# ardcore_V1.net
KiCad netlist of a schematic drawn in EAGLE
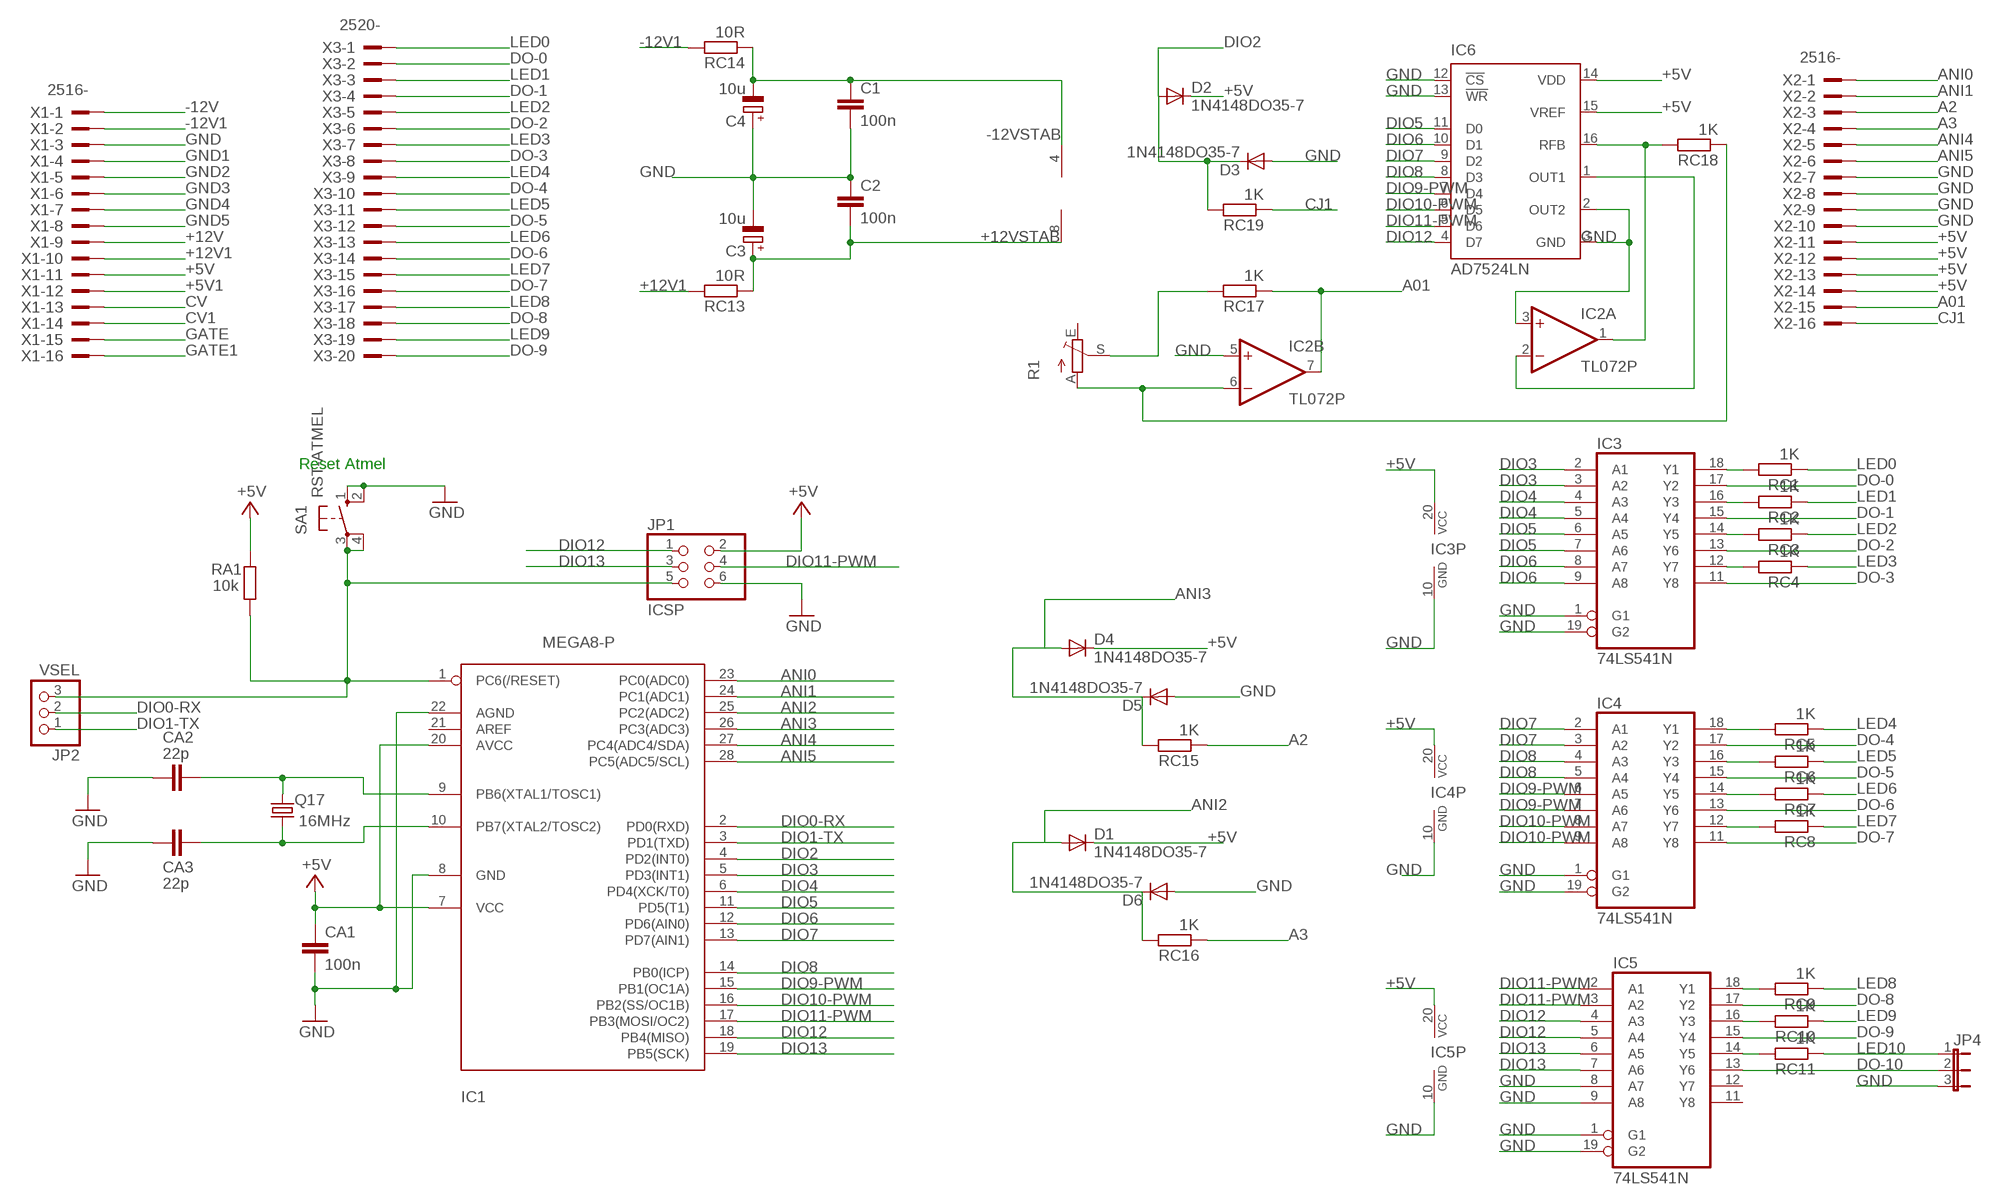
[diagram p0: schematic, sheet 1]

(export (version "E")
  (design (tool "Eeschema 10.0.6"))
  (components
    (comp (ref "C1")
      (value "100n")
      (footprint "eagle-import:C050-025X075")
      (libsource (lib "eagle-import") (part "C-EU050-025X075"))
    )
    (comp (ref "C2")
      (value "100n")
      (footprint "eagle-import:C050-025X075")
      (libsource (lib "eagle-import") (part "C-EU050-025X075"))
    )
    (comp (ref "C3")
      (value "10u")
      (footprint "eagle-import:E2,5-7")
      (libsource (lib "eagle-import") (part "CPOL-EUE2.5-7"))
    )
    (comp (ref "C4")
      (value "10u")
      (footprint "eagle-import:E2,5-7")
      (libsource (lib "eagle-import") (part "CPOL-EUE2.5-7"))
    )
    (comp (ref "CA1")
      (value "100n")
      (footprint "eagle-import:C050-025X075")
      (libsource (lib "eagle-import") (part "C-EU050-025X075"))
    )
    (comp (ref "CA2")
      (value "22p")
      (footprint "eagle-import:C050-025X075")
      (libsource (lib "eagle-import") (part "C-EU050-025X075"))
    )
    (comp (ref "CA3")
      (value "22p")
      (footprint "eagle-import:C050-025X075")
      (libsource (lib "eagle-import") (part "C-EU050-025X075"))
    )
    (comp (ref "D1")
      (value "1N4148DO35-7")
      (footprint "eagle-import:DO35-7")
      (libsource (lib "eagle-import") (part "1N4148DO35-7"))
    )
    (comp (ref "D2")
      (value "1N4148DO35-7")
      (footprint "eagle-import:DO35-7")
      (libsource (lib "eagle-import") (part "1N4148DO35-7"))
    )
    (comp (ref "D3")
      (value "1N4148DO35-7")
      (footprint "eagle-import:DO35-7")
      (libsource (lib "eagle-import") (part "1N4148DO35-7"))
    )
    (comp (ref "D4")
      (value "1N4148DO35-7")
      (footprint "eagle-import:DO35-7")
      (libsource (lib "eagle-import") (part "1N4148DO35-7"))
    )
    (comp (ref "D5")
      (value "1N4148DO35-7")
      (footprint "eagle-import:DO35-7")
      (libsource (lib "eagle-import") (part "1N4148DO35-7"))
    )
    (comp (ref "D6")
      (value "1N4148DO35-7")
      (footprint "eagle-import:DO35-7")
      (libsource (lib "eagle-import") (part "1N4148DO35-7"))
    )
    (comp (ref "IC1")
      (value "MEGA8-P")
      (footprint "eagle-import:DIL28-3")
      (libsource (lib "eagle-import") (part "MEGA8-P"))
    )
    (comp (ref "IC2")
      (value "TL072P")
      (footprint "eagle-import:DIL08")
      (libsource (lib "eagle-import") (part "TL072P"))
    )
    (comp (ref "IC3")
      (value "74LS541N")
      (footprint "eagle-import:DIL20")
      (libsource (lib "eagle-import") (part "74541NLS"))
    )
    (comp (ref "IC4")
      (value "74LS541N")
      (footprint "eagle-import:DIL20")
      (libsource (lib "eagle-import") (part "74541NLS"))
    )
    (comp (ref "IC5")
      (value "74LS541N")
      (footprint "eagle-import:DIL20")
      (libsource (lib "eagle-import") (part "74541NLS"))
    )
    (comp (ref "IC6")
      (value "AD7524LN")
      (footprint "eagle-import:DIL16")
      (fields (field (name "MF") "ALTERA CORPORATION") (field (name "MPN") "AD7524LNZ"))
      (libsource (lib "eagle-import") (part "AD7524NL"))
    )
    (comp (ref "JP1")
      (value "ICSP")
      (footprint "eagle-import:2X03")
      (libsource (lib "eagle-import") (part "PINHD-2X3"))
    )
    (comp (ref "JP2")
      (value "VSEL")
      (footprint "eagle-import:1X03")
      (libsource (lib "eagle-import") (part "PINHD-1X3"))
    )
    (comp (ref "JP4")
      (value "JP2E")
      (footprint "eagle-import:JP2")
      (libsource (lib "eagle-import") (part "JP2E"))
    )
    (comp (ref "Q17")
      (value "16MHz")
      (footprint "eagle-import:HC49_S")
      (libsource (lib "eagle-import") (part "CRYSTALHC49S"))
    )
    (comp (ref "R1")
      (value "TRIM_EU-B64Y")
      (footprint "eagle-import:B64Y")
      (libsource (lib "eagle-import") (part "TRIM_EU-B64Y"))
    )
    (comp (ref "RA1")
      (value "10k")
      (footprint "eagle-import:0207_10")
      (libsource (lib "eagle-import") (part "R-EU_0207/10"))
    )
    (comp (ref "RC1")
      (value "1K")
      (footprint "eagle-import:0207_10")
      (libsource (lib "eagle-import") (part "R-EU_0207/10"))
    )
    (comp (ref "RC2")
      (value "1K")
      (footprint "eagle-import:0207_10")
      (libsource (lib "eagle-import") (part "R-EU_0207/10"))
    )
    (comp (ref "RC3")
      (value "1K")
      (footprint "eagle-import:0207_10")
      (libsource (lib "eagle-import") (part "R-EU_0207/10"))
    )
    (comp (ref "RC4")
      (value "1K")
      (footprint "eagle-import:0207_10")
      (libsource (lib "eagle-import") (part "R-EU_0207/10"))
    )
    (comp (ref "RC5")
      (value "1K")
      (footprint "eagle-import:0207_10")
      (libsource (lib "eagle-import") (part "R-EU_0207/10"))
    )
    (comp (ref "RC6")
      (value "1K")
      (footprint "eagle-import:0207_10")
      (libsource (lib "eagle-import") (part "R-EU_0207/10"))
    )
    (comp (ref "RC7")
      (value "1K")
      (footprint "eagle-import:0207_10")
      (libsource (lib "eagle-import") (part "R-EU_0207/10"))
    )
    (comp (ref "RC8")
      (value "1K")
      (footprint "eagle-import:0207_10")
      (libsource (lib "eagle-import") (part "R-EU_0207/10"))
    )
    (comp (ref "RC9")
      (value "1K")
      (footprint "eagle-import:0207_10")
      (libsource (lib "eagle-import") (part "R-EU_0207/10"))
    )
    (comp (ref "RC10")
      (value "1K")
      (footprint "eagle-import:0207_10")
      (libsource (lib "eagle-import") (part "R-EU_0207/10"))
    )
    (comp (ref "RC11")
      (value "1K")
      (footprint "eagle-import:0207_10")
      (libsource (lib "eagle-import") (part "R-EU_0207/10"))
    )
    (comp (ref "RC13")
      (value "10R")
      (footprint "eagle-import:0207_10")
      (libsource (lib "eagle-import") (part "R-EU_0207/10"))
    )
    (comp (ref "RC14")
      (value "10R")
      (footprint "eagle-import:0207_10")
      (libsource (lib "eagle-import") (part "R-EU_0207/10"))
    )
    (comp (ref "RC15")
      (value "1K")
      (footprint "eagle-import:0207_10")
      (libsource (lib "eagle-import") (part "R-EU_0207/10"))
    )
    (comp (ref "RC16")
      (value "1K")
      (footprint "eagle-import:0207_10")
      (libsource (lib "eagle-import") (part "R-EU_0207/10"))
    )
    (comp (ref "RC17")
      (value "1K")
      (footprint "eagle-import:0207_10")
      (libsource (lib "eagle-import") (part "R-EU_0207/10"))
    )
    (comp (ref "RC18")
      (value "1K")
      (footprint "eagle-import:0207_10")
      (libsource (lib "eagle-import") (part "R-EU_0207/10"))
    )
    (comp (ref "RC19")
      (value "1K")
      (footprint "eagle-import:0207_10")
      (libsource (lib "eagle-import") (part "R-EU_0207/10"))
    )
    (comp (ref "SA1")
      (value "RST-ATMEL")
      (footprint "eagle-import:B3F-10XX")
      (libsource (lib "eagle-import") (part "10-XX"))
    )
    (comp (ref "X1")
      (value "2516-")
      (footprint "eagle-import:PAK100_2500-16")
      (libsource (lib "eagle-import") (part "2516-"))
    )
    (comp (ref "X2")
      (value "2516-")
      (footprint "eagle-import:PAK100_2500-16")
      (libsource (lib "eagle-import") (part "2516-"))
    )
    (comp (ref "X3")
      (value "2520-")
      (footprint "eagle-import:PAK100_2500-20")
      (libsource (lib "eagle-import") (part "2520-"))
    )
  )
  (nets
    (net (code "1") (name "+5V") (class "Default")
      (node (ref "CA1") (pin "1") (pinfunction "1_1") (pintype "passive"))
      (node (ref "D1") (pin "C") (pinfunction "C_C") (pintype "passive"))
      (node (ref "D2") (pin "C") (pinfunction "C_C") (pintype "passive"))
      (node (ref "D4") (pin "C") (pinfunction "C_C") (pintype "passive"))
      (node (ref "IC1") (pin "20") (pinfunction "AVCC_20") (pintype "power_in"))
      (node (ref "IC1") (pin "7") (pinfunction "VCC_7") (pintype "power_in"))
      (node (ref "IC3") (pin "20") (pinfunction "VCC_20") (pintype "power_in"))
      (node (ref "IC4") (pin "20") (pinfunction "VCC_20") (pintype "power_in"))
      (node (ref "IC5") (pin "20") (pinfunction "VCC_20") (pintype "power_in"))
      (node (ref "IC6") (pin "14") (pinfunction "VDD_14") (pintype "power_in"))
      (node (ref "IC6") (pin "15") (pinfunction "VREF_15") (pintype "input"))
      (node (ref "JP1") (pin "2") (pinfunction "2_2") (pintype "passive"))
      (node (ref "RA1") (pin "1") (pinfunction "1_1") (pintype "passive"))
      (node (ref "X1") (pin "11") (pinfunction "KL_11") (pintype "passive"))
      (node (ref "X2") (pin "11") (pinfunction "KL_11") (pintype "passive"))
      (node (ref "X2") (pin "12") (pinfunction "KL_12") (pintype "passive"))
      (node (ref "X2") (pin "13") (pinfunction "KL_13") (pintype "passive"))
      (node (ref "X2") (pin "14") (pinfunction "KL_14") (pintype "passive"))
    )
    (net (code "2") (name "/+5V1") (class "Default")
      (node (ref "X1") (pin "12") (pinfunction "KL_12") (pintype "passive"))
    )
    (net (code "3") (name "/+12V") (class "Default")
      (node (ref "X1") (pin "9") (pinfunction "KL_9") (pintype "passive"))
    )
    (net (code "4") (name "/+12V1") (class "Default")
      (node (ref "RC13") (pin "2") (pinfunction "2_2") (pintype "passive"))
      (node (ref "X1") (pin "10") (pinfunction "KL_10") (pintype "passive"))
    )
    (net (code "5") (name "/+12VSTAB") (class "Default")
      (node (ref "C2") (pin "2") (pinfunction "2_2") (pintype "passive"))
      (node (ref "C3") (pin "+") (pinfunction "+_+") (pintype "passive"))
      (node (ref "IC2") (pin "8") (pinfunction "V+_8") (pintype "power_in"))
      (node (ref "RC13") (pin "1") (pinfunction "1_1") (pintype "passive"))
    )
    (net (code "6") (name "/-12V") (class "Default")
      (node (ref "X1") (pin "1") (pinfunction "KL_1") (pintype "passive"))
    )
    (net (code "7") (name "/-12V1") (class "Default")
      (node (ref "RC14") (pin "2") (pinfunction "2_2") (pintype "passive"))
      (node (ref "X1") (pin "2") (pinfunction "KL_2") (pintype "passive"))
    )
    (net (code "8") (name "/-12VSTAB") (class "Default")
      (node (ref "C1") (pin "1") (pinfunction "1_1") (pintype "passive"))
      (node (ref "C4") (pin "-") (pinfunction "-_-") (pintype "passive"))
      (node (ref "IC2") (pin "4") (pinfunction "V-_4") (pintype "power_in"))
      (node (ref "RC14") (pin "1") (pinfunction "1_1") (pintype "passive"))
    )
    (net (code "9") (name "/A01") (class "Default")
      (node (ref "IC2") (pin "7") (pinfunction "OUT_7") (pintype "output"))
      (node (ref "RC17") (pin "1") (pinfunction "1_1") (pintype "passive"))
      (node (ref "X2") (pin "15") (pinfunction "KL_15") (pintype "passive"))
    )
    (net (code "10") (name "/A2") (class "Default")
      (node (ref "RC15") (pin "1") (pinfunction "1_1") (pintype "passive"))
      (node (ref "X2") (pin "3") (pinfunction "KL_3") (pintype "passive"))
    )
    (net (code "11") (name "/A3") (class "Default")
      (node (ref "RC16") (pin "1") (pinfunction "1_1") (pintype "passive"))
      (node (ref "X2") (pin "4") (pinfunction "KL_4") (pintype "passive"))
    )
    (net (code "12") (name "/ANI0") (class "Default")
      (node (ref "IC1") (pin "23") (pinfunction "PC0(ADC0)_23") (pintype "bidirectional"))
      (node (ref "X2") (pin "1") (pinfunction "KL_1") (pintype "passive"))
    )
    (net (code "13") (name "/ANI1") (class "Default")
      (node (ref "IC1") (pin "24") (pinfunction "PC1(ADC1)_24") (pintype "bidirectional"))
      (node (ref "X2") (pin "2") (pinfunction "KL_2") (pintype "passive"))
    )
    (net (code "14") (name "/ANI2") (class "Default")
      (node (ref "D1") (pin "A") (pinfunction "A_A") (pintype "passive"))
      (node (ref "D6") (pin "C") (pinfunction "C_C") (pintype "passive"))
      (node (ref "IC1") (pin "25") (pinfunction "PC2(ADC2)_25") (pintype "bidirectional"))
      (node (ref "RC16") (pin "2") (pinfunction "2_2") (pintype "passive"))
    )
    (net (code "15") (name "/ANI3") (class "Default")
      (node (ref "D4") (pin "A") (pinfunction "A_A") (pintype "passive"))
      (node (ref "D5") (pin "C") (pinfunction "C_C") (pintype "passive"))
      (node (ref "IC1") (pin "26") (pinfunction "PC3(ADC3)_26") (pintype "bidirectional"))
      (node (ref "RC15") (pin "2") (pinfunction "2_2") (pintype "passive"))
    )
    (net (code "16") (name "/ANI4") (class "Default")
      (node (ref "IC1") (pin "27") (pinfunction "PC4(ADC4/SDA)_27") (pintype "bidirectional"))
      (node (ref "X2") (pin "5") (pinfunction "KL_5") (pintype "passive"))
    )
    (net (code "17") (name "/ANI5") (class "Default")
      (node (ref "IC1") (pin "28") (pinfunction "PC5(ADC5/SCL)_28") (pintype "bidirectional"))
      (node (ref "X2") (pin "6") (pinfunction "KL_6") (pintype "passive"))
    )
    (net (code "18") (name "/CJ1") (class "Default")
      (node (ref "RC19") (pin "1") (pinfunction "1_1") (pintype "passive"))
      (node (ref "X2") (pin "16") (pinfunction "KL_16") (pintype "passive"))
    )
    (net (code "19") (name "/CV") (class "Default")
      (node (ref "X1") (pin "13") (pinfunction "KL_13") (pintype "passive"))
    )
    (net (code "20") (name "/CV1") (class "Default")
      (node (ref "X1") (pin "14") (pinfunction "KL_14") (pintype "passive"))
    )
    (net (code "21") (name "/DIO0-RX") (class "Default")
      (node (ref "IC1") (pin "2") (pinfunction "PD0(RXD)_2") (pintype "bidirectional"))
      (node (ref "JP2") (pin "2") (pinfunction "2_2") (pintype "passive"))
    )
    (net (code "22") (name "/DIO1-TX") (class "Default")
      (node (ref "IC1") (pin "3") (pinfunction "PD1(TXD)_3") (pintype "bidirectional"))
      (node (ref "JP2") (pin "1") (pinfunction "1_1") (pintype "passive"))
    )
    (net (code "23") (name "/DIO2") (class "Default")
      (node (ref "D2") (pin "A") (pinfunction "A_A") (pintype "passive"))
      (node (ref "D3") (pin "C") (pinfunction "C_C") (pintype "passive"))
      (node (ref "IC1") (pin "4") (pinfunction "PD2(INT0)_4") (pintype "bidirectional"))
      (node (ref "RC19") (pin "2") (pinfunction "2_2") (pintype "passive"))
    )
    (net (code "24") (name "/DIO3") (class "Default")
      (node (ref "IC1") (pin "5") (pinfunction "PD3(INT1)_5") (pintype "bidirectional"))
      (node (ref "IC3") (pin "2") (pinfunction "A1_2") (pintype "input"))
      (node (ref "IC3") (pin "3") (pinfunction "A2_3") (pintype "input"))
    )
    (net (code "25") (name "/DIO4") (class "Default")
      (node (ref "IC1") (pin "6") (pinfunction "PD4(XCK/T0)_6") (pintype "bidirectional"))
      (node (ref "IC3") (pin "4") (pinfunction "A3_4") (pintype "input"))
      (node (ref "IC3") (pin "5") (pinfunction "A4_5") (pintype "input"))
    )
    (net (code "26") (name "/DIO5") (class "Default")
      (node (ref "IC1") (pin "11") (pinfunction "PD5(T1)_11") (pintype "bidirectional"))
      (node (ref "IC3") (pin "6") (pinfunction "A5_6") (pintype "input"))
      (node (ref "IC3") (pin "7") (pinfunction "A6_7") (pintype "input"))
      (node (ref "IC6") (pin "11") (pinfunction "D0_11") (pintype "input"))
    )
    (net (code "27") (name "/DIO6") (class "Default")
      (node (ref "IC1") (pin "12") (pinfunction "PD6(AIN0)_12") (pintype "bidirectional"))
      (node (ref "IC3") (pin "8") (pinfunction "A7_8") (pintype "input"))
      (node (ref "IC3") (pin "9") (pinfunction "A8_9") (pintype "input"))
      (node (ref "IC6") (pin "10") (pinfunction "D1_10") (pintype "input"))
    )
    (net (code "28") (name "/DIO7") (class "Default")
      (node (ref "IC1") (pin "13") (pinfunction "PD7(AIN1)_13") (pintype "bidirectional"))
      (node (ref "IC4") (pin "2") (pinfunction "A1_2") (pintype "input"))
      (node (ref "IC4") (pin "3") (pinfunction "A2_3") (pintype "input"))
      (node (ref "IC6") (pin "9") (pinfunction "D2_9") (pintype "input"))
    )
    (net (code "29") (name "/DIO8") (class "Default")
      (node (ref "IC1") (pin "14") (pinfunction "PB0(ICP)_14") (pintype "bidirectional"))
      (node (ref "IC4") (pin "4") (pinfunction "A3_4") (pintype "input"))
      (node (ref "IC4") (pin "5") (pinfunction "A4_5") (pintype "input"))
      (node (ref "IC6") (pin "8") (pinfunction "D3_8") (pintype "input"))
    )
    (net (code "30") (name "/DIO9-PWM") (class "Default")
      (node (ref "IC1") (pin "15") (pinfunction "PB1(OC1A)_15") (pintype "bidirectional"))
      (node (ref "IC4") (pin "6") (pinfunction "A5_6") (pintype "input"))
      (node (ref "IC4") (pin "7") (pinfunction "A6_7") (pintype "input"))
      (node (ref "IC6") (pin "7") (pinfunction "D4_7") (pintype "input"))
    )
    (net (code "31") (name "/DIO10-PWM") (class "Default")
      (node (ref "IC1") (pin "16") (pinfunction "PB2(SS/OC1B)_16") (pintype "bidirectional"))
      (node (ref "IC4") (pin "8") (pinfunction "A7_8") (pintype "input"))
      (node (ref "IC4") (pin "9") (pinfunction "A8_9") (pintype "input"))
      (node (ref "IC6") (pin "6") (pinfunction "D5_6") (pintype "input"))
    )
    (net (code "32") (name "/DIO11-PWM") (class "Default")
      (node (ref "IC1") (pin "17") (pinfunction "PB3(MOSI/OC2)_17") (pintype "bidirectional"))
      (node (ref "IC5") (pin "2") (pinfunction "A1_2") (pintype "input"))
      (node (ref "IC5") (pin "3") (pinfunction "A2_3") (pintype "input"))
      (node (ref "IC6") (pin "5") (pinfunction "D6_5") (pintype "input"))
      (node (ref "JP1") (pin "4") (pinfunction "4_4") (pintype "passive"))
    )
    (net (code "33") (name "/DIO12") (class "Default")
      (node (ref "IC1") (pin "18") (pinfunction "PB4(MISO)_18") (pintype "bidirectional"))
      (node (ref "IC5") (pin "4") (pinfunction "A3_4") (pintype "input"))
      (node (ref "IC5") (pin "5") (pinfunction "A4_5") (pintype "input"))
      (node (ref "IC6") (pin "4") (pinfunction "D7_4") (pintype "input"))
      (node (ref "JP1") (pin "1") (pinfunction "1_1") (pintype "passive"))
    )
    (net (code "34") (name "/DIO13") (class "Default")
      (node (ref "IC1") (pin "19") (pinfunction "PB5(SCK)_19") (pintype "bidirectional"))
      (node (ref "IC5") (pin "6") (pinfunction "A5_6") (pintype "input"))
      (node (ref "IC5") (pin "7") (pinfunction "A6_7") (pintype "input"))
      (node (ref "JP1") (pin "3") (pinfunction "3_3") (pintype "passive"))
    )
    (net (code "35") (name "/DO-0") (class "Default")
      (node (ref "IC3") (pin "17") (pinfunction "Y2_17") (pintype "tri_state"))
      (node (ref "X3") (pin "2") (pinfunction "KL_2") (pintype "passive"))
    )
    (net (code "36") (name "/DO-1") (class "Default")
      (node (ref "IC3") (pin "15") (pinfunction "Y4_15") (pintype "tri_state"))
      (node (ref "X3") (pin "4") (pinfunction "KL_4") (pintype "passive"))
    )
    (net (code "37") (name "/DO-2") (class "Default")
      (node (ref "IC3") (pin "13") (pinfunction "Y6_13") (pintype "tri_state"))
      (node (ref "X3") (pin "6") (pinfunction "KL_6") (pintype "passive"))
    )
    (net (code "38") (name "/DO-3") (class "Default")
      (node (ref "IC3") (pin "11") (pinfunction "Y8_11") (pintype "tri_state"))
      (node (ref "X3") (pin "8") (pinfunction "KL_8") (pintype "passive"))
    )
    (net (code "39") (name "/DO-4") (class "Default")
      (node (ref "IC4") (pin "17") (pinfunction "Y2_17") (pintype "tri_state"))
      (node (ref "X3") (pin "10") (pinfunction "KL_10") (pintype "passive"))
    )
    (net (code "40") (name "/DO-5") (class "Default")
      (node (ref "IC4") (pin "15") (pinfunction "Y4_15") (pintype "tri_state"))
      (node (ref "X3") (pin "12") (pinfunction "KL_12") (pintype "passive"))
    )
    (net (code "41") (name "/DO-6") (class "Default")
      (node (ref "IC4") (pin "13") (pinfunction "Y6_13") (pintype "tri_state"))
      (node (ref "X3") (pin "14") (pinfunction "KL_14") (pintype "passive"))
    )
    (net (code "42") (name "/DO-7") (class "Default")
      (node (ref "IC4") (pin "11") (pinfunction "Y8_11") (pintype "tri_state"))
      (node (ref "X3") (pin "16") (pinfunction "KL_16") (pintype "passive"))
    )
    (net (code "43") (name "/DO-8") (class "Default")
      (node (ref "IC5") (pin "17") (pinfunction "Y2_17") (pintype "tri_state"))
      (node (ref "X3") (pin "18") (pinfunction "KL_18") (pintype "passive"))
    )
    (net (code "44") (name "/DO-9") (class "Default")
      (node (ref "IC5") (pin "15") (pinfunction "Y4_15") (pintype "tri_state"))
      (node (ref "X3") (pin "20") (pinfunction "KL_20") (pintype "passive"))
    )
    (net (code "45") (name "/DO-10") (class "Default")
      (node (ref "IC5") (pin "13") (pinfunction "Y6_13") (pintype "tri_state"))
      (node (ref "JP4") (pin "2") (pinfunction "2_2") (pintype "passive"))
    )
    (net (code "46") (name "/GATE") (class "Default")
      (node (ref "X1") (pin "15") (pinfunction "KL_15") (pintype "passive"))
    )
    (net (code "47") (name "/GATE1") (class "Default")
      (node (ref "X1") (pin "16") (pinfunction "KL_16") (pintype "passive"))
    )
    (net (code "48") (name "/GND1") (class "Default")
      (node (ref "X1") (pin "4") (pinfunction "KL_4") (pintype "passive"))
    )
    (net (code "49") (name "/GND2") (class "Default")
      (node (ref "X1") (pin "5") (pinfunction "KL_5") (pintype "passive"))
    )
    (net (code "50") (name "/GND3") (class "Default")
      (node (ref "X1") (pin "6") (pinfunction "KL_6") (pintype "passive"))
    )
    (net (code "51") (name "/GND4") (class "Default")
      (node (ref "X1") (pin "7") (pinfunction "KL_7") (pintype "passive"))
    )
    (net (code "52") (name "/GND5") (class "Default")
      (node (ref "X1") (pin "8") (pinfunction "KL_8") (pintype "passive"))
    )
    (net (code "53") (name "/LED0") (class "Default")
      (node (ref "RC1") (pin "1") (pinfunction "1_1") (pintype "passive"))
      (node (ref "X3") (pin "1") (pinfunction "KL_1") (pintype "passive"))
    )
    (net (code "54") (name "/LED1") (class "Default")
      (node (ref "RC2") (pin "1") (pinfunction "1_1") (pintype "passive"))
      (node (ref "X3") (pin "3") (pinfunction "KL_3") (pintype "passive"))
    )
    (net (code "55") (name "/LED2") (class "Default")
      (node (ref "RC3") (pin "1") (pinfunction "1_1") (pintype "passive"))
      (node (ref "X3") (pin "5") (pinfunction "KL_5") (pintype "passive"))
    )
    (net (code "56") (name "/LED3") (class "Default")
      (node (ref "RC4") (pin "1") (pinfunction "1_1") (pintype "passive"))
      (node (ref "X3") (pin "7") (pinfunction "KL_7") (pintype "passive"))
    )
    (net (code "57") (name "/LED4") (class "Default")
      (node (ref "RC5") (pin "1") (pinfunction "1_1") (pintype "passive"))
      (node (ref "X3") (pin "9") (pinfunction "KL_9") (pintype "passive"))
    )
    (net (code "58") (name "/LED5") (class "Default")
      (node (ref "RC6") (pin "1") (pinfunction "1_1") (pintype "passive"))
      (node (ref "X3") (pin "11") (pinfunction "KL_11") (pintype "passive"))
    )
    (net (code "59") (name "/LED6") (class "Default")
      (node (ref "RC7") (pin "1") (pinfunction "1_1") (pintype "passive"))
      (node (ref "X3") (pin "13") (pinfunction "KL_13") (pintype "passive"))
    )
    (net (code "60") (name "/LED7") (class "Default")
      (node (ref "RC8") (pin "1") (pinfunction "1_1") (pintype "passive"))
      (node (ref "X3") (pin "15") (pinfunction "KL_15") (pintype "passive"))
    )
    (net (code "61") (name "/LED8") (class "Default")
      (node (ref "RC9") (pin "1") (pinfunction "1_1") (pintype "passive"))
      (node (ref "X3") (pin "17") (pinfunction "KL_17") (pintype "passive"))
    )
    (net (code "62") (name "/LED9") (class "Default")
      (node (ref "RC10") (pin "1") (pinfunction "1_1") (pintype "passive"))
      (node (ref "X3") (pin "19") (pinfunction "KL_19") (pintype "passive"))
    )
    (net (code "63") (name "/LED10") (class "Default")
      (node (ref "JP4") (pin "1") (pinfunction "1_1") (pintype "passive"))
      (node (ref "RC11") (pin "1") (pinfunction "1_1") (pintype "passive"))
    )
    (net (code "64") (name "GND") (class "Default")
      (node (ref "C1") (pin "2") (pinfunction "2_2") (pintype "passive"))
      (node (ref "C2") (pin "1") (pinfunction "1_1") (pintype "passive"))
      (node (ref "C3") (pin "-") (pinfunction "-_-") (pintype "passive"))
      (node (ref "C4") (pin "+") (pinfunction "+_+") (pintype "passive"))
      (node (ref "CA1") (pin "2") (pinfunction "2_2") (pintype "passive"))
      (node (ref "CA2") (pin "2") (pinfunction "2_2") (pintype "passive"))
      (node (ref "CA3") (pin "2") (pinfunction "2_2") (pintype "passive"))
      (node (ref "D3") (pin "A") (pinfunction "A_A") (pintype "passive"))
      (node (ref "D5") (pin "A") (pinfunction "A_A") (pintype "passive"))
      (node (ref "D6") (pin "A") (pinfunction "A_A") (pintype "passive"))
      (node (ref "IC1") (pin "22") (pinfunction "AGND_22") (pintype "power_in"))
      (node (ref "IC1") (pin "8") (pinfunction "GND_8") (pintype "power_in"))
      (node (ref "IC2") (pin "3") (pinfunction "+IN_3") (pintype "input"))
      (node (ref "IC2") (pin "5") (pinfunction "+IN_5") (pintype "input"))
      (node (ref "IC3") (pin "1") (pinfunction "G1_1") (pintype "input"))
      (node (ref "IC3") (pin "10") (pinfunction "GND_10") (pintype "power_in"))
      (node (ref "IC3") (pin "19") (pinfunction "G2_19") (pintype "input"))
      (node (ref "IC4") (pin "1") (pinfunction "G1_1") (pintype "input"))
      (node (ref "IC4") (pin "10") (pinfunction "GND_10") (pintype "power_in"))
      (node (ref "IC4") (pin "19") (pinfunction "G2_19") (pintype "input"))
      (node (ref "IC5") (pin "1") (pinfunction "G1_1") (pintype "input"))
      (node (ref "IC5") (pin "10") (pinfunction "GND_10") (pintype "power_in"))
      (node (ref "IC5") (pin "19") (pinfunction "G2_19") (pintype "input"))
      (node (ref "IC5") (pin "8") (pinfunction "A7_8") (pintype "input"))
      (node (ref "IC5") (pin "9") (pinfunction "A8_9") (pintype "input"))
      (node (ref "IC6") (pin "12") (pinfunction "~{CS}_12") (pintype "input"))
      (node (ref "IC6") (pin "13") (pinfunction "~{WR}_13") (pintype "input"))
      (node (ref "IC6") (pin "2") (pinfunction "OUT2_2") (pintype "passive"))
      (node (ref "IC6") (pin "3") (pinfunction "GND_3") (pintype "power_in"))
      (node (ref "JP1") (pin "6") (pinfunction "6_6") (pintype "passive"))
      (node (ref "JP4") (pin "3") (pinfunction "3_3") (pintype "passive"))
      (node (ref "SA1") (pin "1") (pinfunction "S_1") (pintype "passive"))
      (node (ref "SA1") (pin "2") (pinfunction "S1_2") (pintype "passive"))
      (node (ref "X1") (pin "3") (pinfunction "KL_3") (pintype "passive"))
      (node (ref "X2") (pin "10") (pinfunction "KL_10") (pintype "passive"))
      (node (ref "X2") (pin "7") (pinfunction "KL_7") (pintype "passive"))
      (node (ref "X2") (pin "8") (pinfunction "KL_8") (pintype "passive"))
      (node (ref "X2") (pin "9") (pinfunction "KL_9") (pintype "passive"))
    )
    (net (code "65") (name "Net-(IC1-PB6(XTAL1{slash}TOSC1))") (class "Default")
      (node (ref "CA2") (pin "1") (pinfunction "1_1") (pintype "passive"))
      (node (ref "IC1") (pin "9") (pinfunction "PB6(XTAL1/TOSC1)_9") (pintype "bidirectional"))
      (node (ref "Q17") (pin "2") (pinfunction "2_2") (pintype "passive"))
    )
    (net (code "66") (name "Net-(IC1-PB7(XTAL2{slash}TOSC2))") (class "Default")
      (node (ref "CA3") (pin "1") (pinfunction "1_1") (pintype "passive"))
      (node (ref "IC1") (pin "10") (pinfunction "PB7(XTAL2/TOSC2)_10") (pintype "bidirectional"))
      (node (ref "Q17") (pin "1") (pinfunction "1_1") (pintype "passive"))
    )
    (net (code "67") (name "Net-(IC1-PC6({slash}RESET))") (class "Default")
      (node (ref "IC1") (pin "1") (pinfunction "PC6(/RESET)_1") (pintype "bidirectional"))
      (node (ref "JP1") (pin "5") (pinfunction "5_5") (pintype "passive"))
      (node (ref "JP2") (pin "3") (pinfunction "3_3") (pintype "passive"))
      (node (ref "RA1") (pin "2") (pinfunction "2_2") (pintype "passive"))
      (node (ref "SA1") (pin "3") (pinfunction "P_3") (pintype "passive"))
      (node (ref "SA1") (pin "4") (pinfunction "P1_4") (pintype "passive"))
    )
    (net (code "68") (name "Net-(IC2A--IN)") (class "Default")
      (node (ref "IC2") (pin "2") (pinfunction "-IN_2") (pintype "input"))
      (node (ref "IC6") (pin "1") (pinfunction "OUT1_1") (pintype "passive"))
    )
    (net (code "69") (name "Net-(IC2A-OUT)") (class "Default")
      (node (ref "IC2") (pin "1") (pinfunction "OUT_1") (pintype "output"))
      (node (ref "IC6") (pin "16") (pinfunction "RFB_16") (pintype "passive"))
      (node (ref "RC18") (pin "2") (pinfunction "2_2") (pintype "passive"))
    )
    (net (code "70") (name "Net-(IC2B--IN)") (class "Default")
      (node (ref "IC2") (pin "6") (pinfunction "-IN_6") (pintype "input"))
      (node (ref "R1") (pin "A") (pinfunction "A_A") (pintype "passive"))
      (node (ref "RC18") (pin "1") (pinfunction "1_1") (pintype "passive"))
    )
    (net (code "71") (name "Net-(IC3A-Y1)") (class "Default")
      (node (ref "IC3") (pin "18") (pinfunction "Y1_18") (pintype "tri_state"))
      (node (ref "RC1") (pin "2") (pinfunction "2_2") (pintype "passive"))
    )
    (net (code "72") (name "Net-(IC3A-Y3)") (class "Default")
      (node (ref "IC3") (pin "16") (pinfunction "Y3_16") (pintype "tri_state"))
      (node (ref "RC2") (pin "2") (pinfunction "2_2") (pintype "passive"))
    )
    (net (code "73") (name "Net-(IC3A-Y5)") (class "Default")
      (node (ref "IC3") (pin "14") (pinfunction "Y5_14") (pintype "tri_state"))
      (node (ref "RC3") (pin "2") (pinfunction "2_2") (pintype "passive"))
    )
    (net (code "74") (name "Net-(IC3A-Y7)") (class "Default")
      (node (ref "IC3") (pin "12") (pinfunction "Y7_12") (pintype "tri_state"))
      (node (ref "RC4") (pin "2") (pinfunction "2_2") (pintype "passive"))
    )
    (net (code "75") (name "Net-(IC4A-Y1)") (class "Default")
      (node (ref "IC4") (pin "18") (pinfunction "Y1_18") (pintype "tri_state"))
      (node (ref "RC5") (pin "2") (pinfunction "2_2") (pintype "passive"))
    )
    (net (code "76") (name "Net-(IC4A-Y3)") (class "Default")
      (node (ref "IC4") (pin "16") (pinfunction "Y3_16") (pintype "tri_state"))
      (node (ref "RC6") (pin "2") (pinfunction "2_2") (pintype "passive"))
    )
    (net (code "77") (name "Net-(IC4A-Y5)") (class "Default")
      (node (ref "IC4") (pin "14") (pinfunction "Y5_14") (pintype "tri_state"))
      (node (ref "RC7") (pin "2") (pinfunction "2_2") (pintype "passive"))
    )
    (net (code "78") (name "Net-(IC4A-Y7)") (class "Default")
      (node (ref "IC4") (pin "12") (pinfunction "Y7_12") (pintype "tri_state"))
      (node (ref "RC8") (pin "2") (pinfunction "2_2") (pintype "passive"))
    )
    (net (code "79") (name "Net-(IC5A-Y1)") (class "Default")
      (node (ref "IC5") (pin "18") (pinfunction "Y1_18") (pintype "tri_state"))
      (node (ref "RC9") (pin "2") (pinfunction "2_2") (pintype "passive"))
    )
    (net (code "80") (name "Net-(IC5A-Y3)") (class "Default")
      (node (ref "IC5") (pin "16") (pinfunction "Y3_16") (pintype "tri_state"))
      (node (ref "RC10") (pin "2") (pinfunction "2_2") (pintype "passive"))
    )
    (net (code "81") (name "Net-(IC5A-Y5)") (class "Default")
      (node (ref "IC5") (pin "14") (pinfunction "Y5_14") (pintype "tri_state"))
      (node (ref "RC11") (pin "2") (pinfunction "2_2") (pintype "passive"))
    )
    (net (code "82") (name "Net-(R1-PadS)") (class "Default")
      (node (ref "R1") (pin "S") (pinfunction "S_S") (pintype "passive"))
      (node (ref "RC17") (pin "2") (pinfunction "2_2") (pintype "passive"))
    )
    (net (code "83") (name "unconnected-(IC1-AREF-Pad21)") (class "Default")
      (node (ref "IC1") (pin "21") (pinfunction "AREF_21") (pintype "passive"))
    )
    (net (code "84") (name "unconnected-(IC5A-Y7-Pad12)") (class "Default")
      (node (ref "IC5") (pin "12") (pinfunction "Y7_12") (pintype "tri_state"))
    )
    (net (code "85") (name "unconnected-(IC5A-Y8-Pad11)") (class "Default")
      (node (ref "IC5") (pin "11") (pinfunction "Y8_11") (pintype "tri_state"))
    )
    (net (code "86") (name "unconnected-(R1-PadE)") (class "Default")
      (node (ref "R1") (pin "E") (pinfunction "E_E") (pintype "passive"))
    )
  )
)
